# ProDoc_HyperCardReader_2024-07-05.net
KiCad netlist of a schematic drawn in EasyEDA Pro
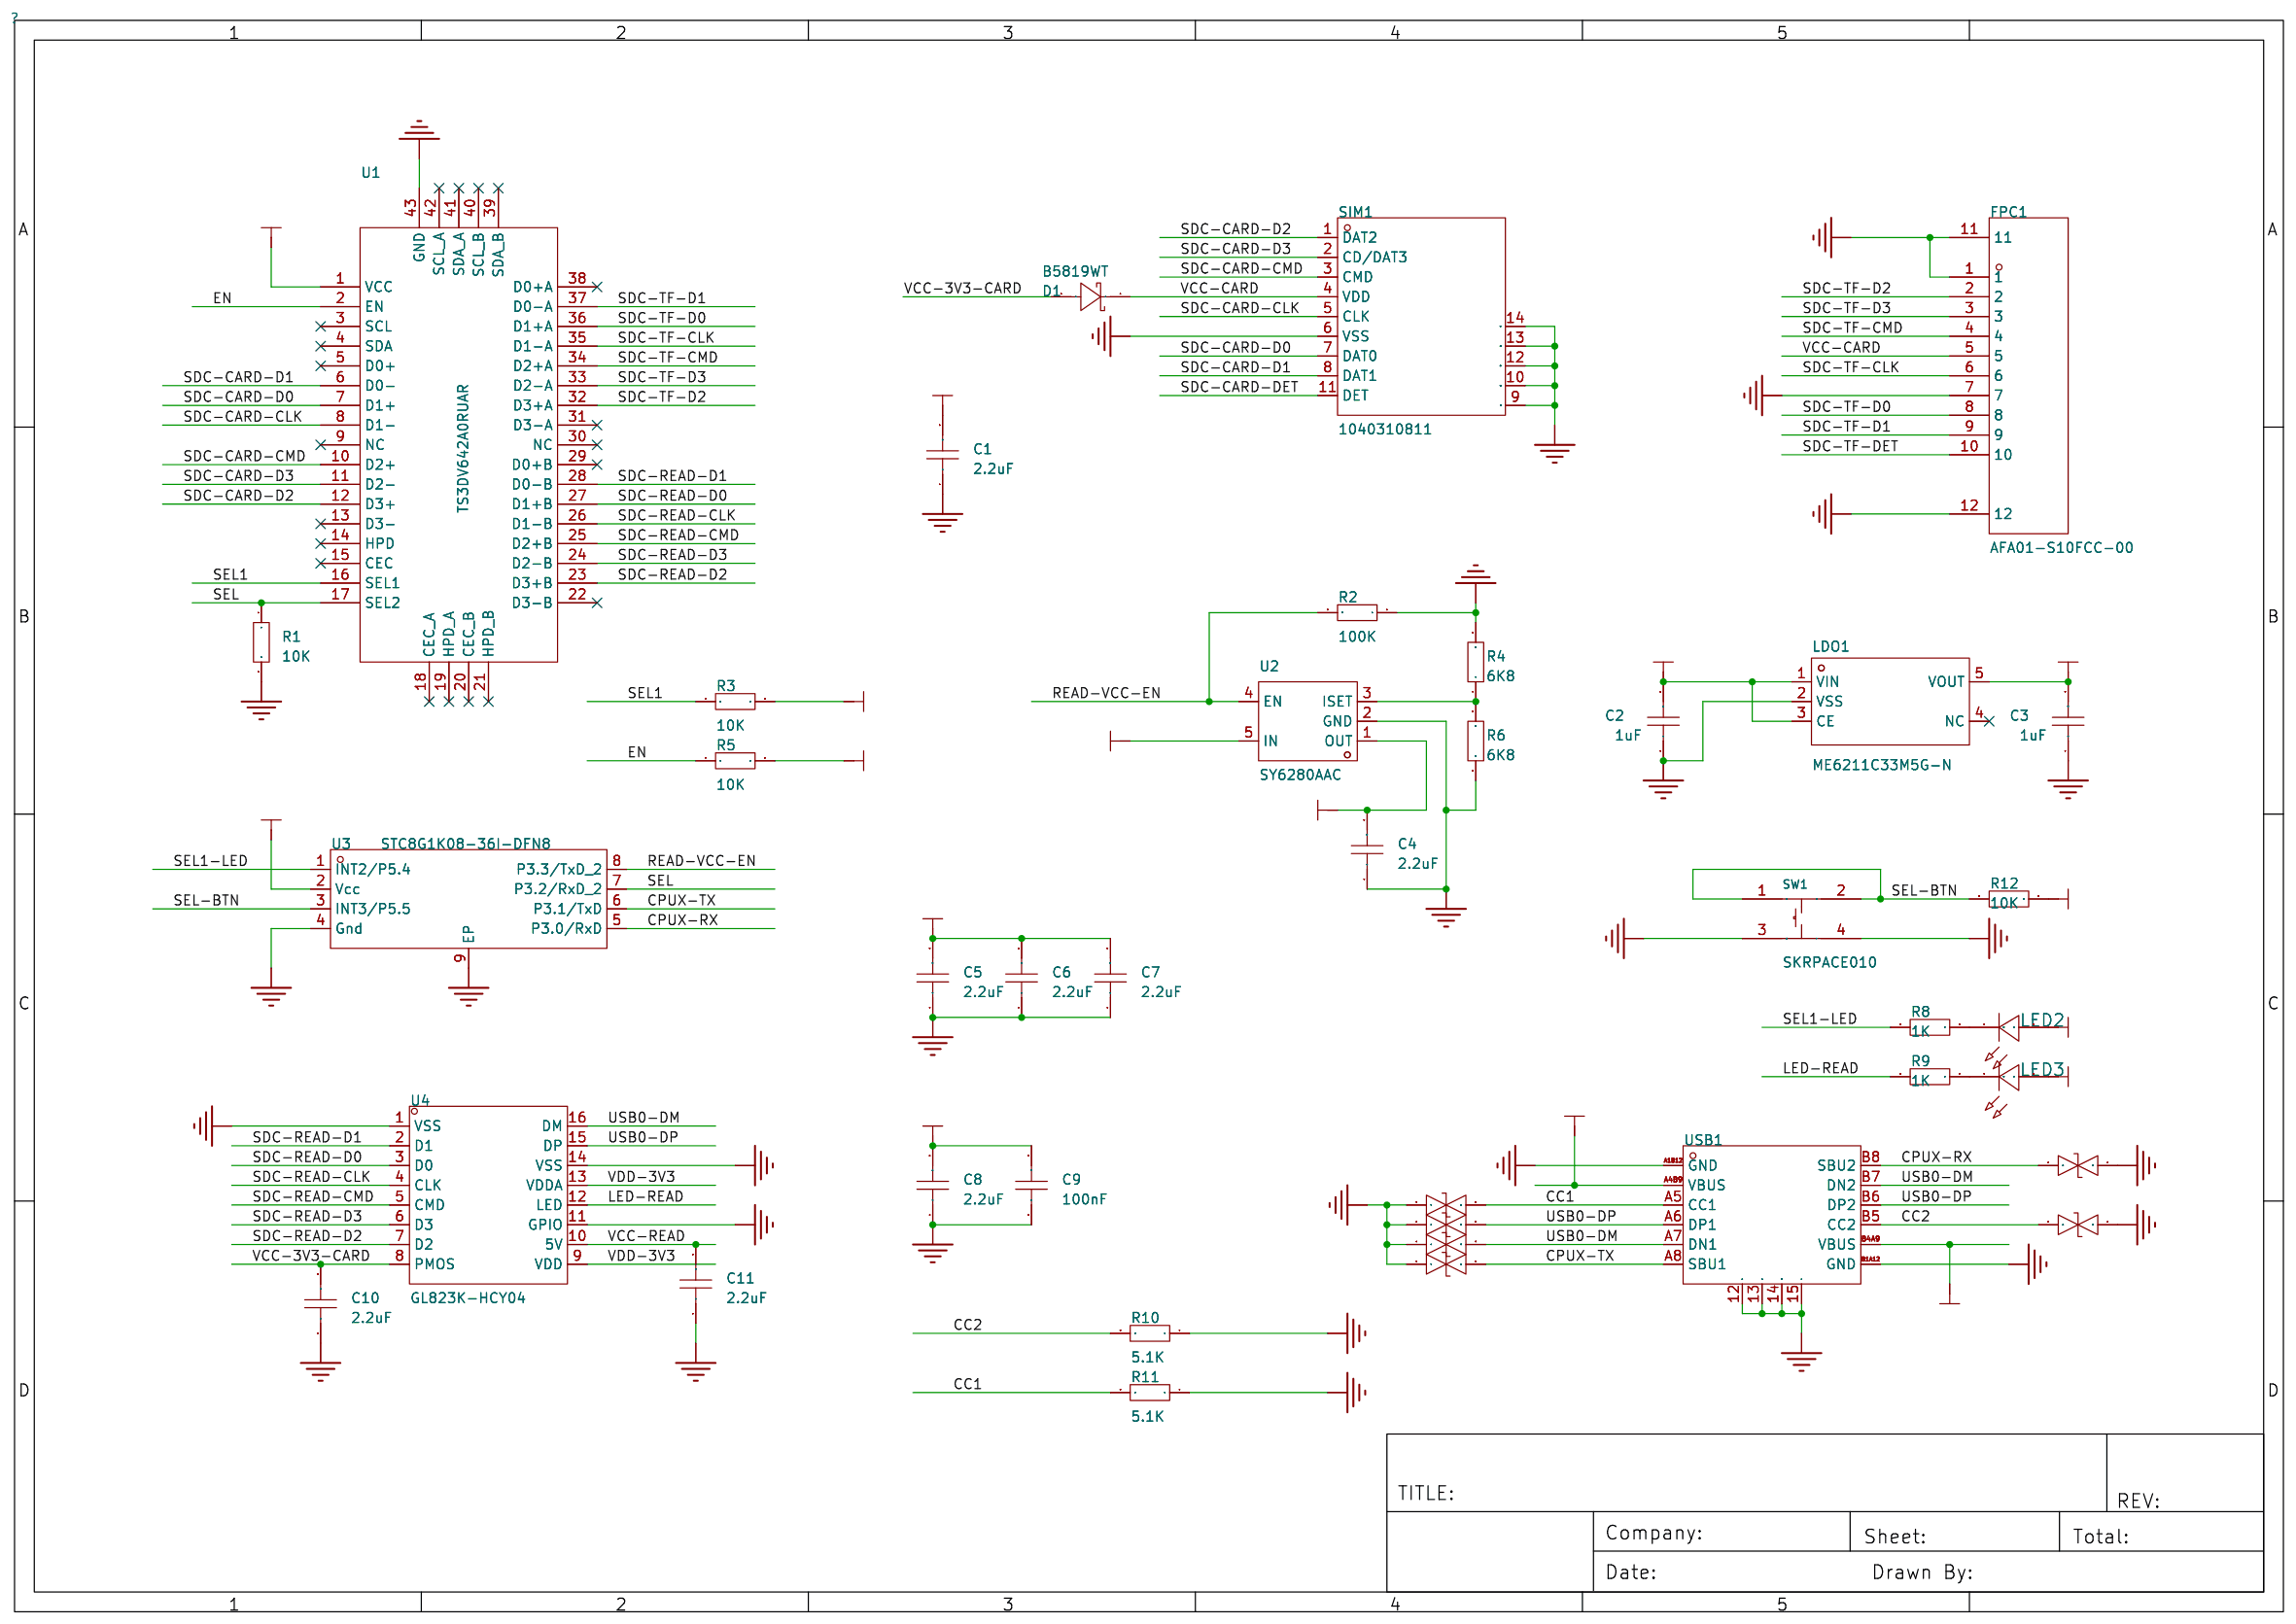
[diagram p0: schematic sheet]

(export (version "E")
  (design (tool "Eeschema 10.0.6"))
  (components
    (comp (ref "C1")
      (value "2.2uF")
      (footprint "easyedapro:C0402")
      (libsource (lib "easyedapro") (part "CapAcitance"))
    )
    (comp (ref "C2")
      (value "1uF")
      (footprint "easyedapro:C0402")
      (libsource (lib "easyedapro") (part "CapAcitance"))
    )
    (comp (ref "C3")
      (value "1uF")
      (footprint "easyedapro:C0402")
      (libsource (lib "easyedapro") (part "CapAcitance"))
    )
    (comp (ref "C4")
      (value "2.2uF")
      (footprint "easyedapro:C0402")
      (libsource (lib "easyedapro") (part "CapAcitance"))
    )
    (comp (ref "C5")
      (value "2.2uF")
      (footprint "easyedapro:C0402")
      (libsource (lib "easyedapro") (part "CapAcitance"))
    )
    (comp (ref "C6")
      (value "2.2uF")
      (footprint "easyedapro:C0402")
      (libsource (lib "easyedapro") (part "CapAcitance"))
    )
    (comp (ref "C7")
      (value "2.2uF")
      (footprint "easyedapro:C0402")
      (libsource (lib "easyedapro") (part "CapAcitance"))
    )
    (comp (ref "C8")
      (value "2.2uF")
      (footprint "easyedapro:C0402")
      (libsource (lib "easyedapro") (part "CapAcitance"))
    )
    (comp (ref "C9")
      (value "100nF")
      (footprint "easyedapro:C0402")
      (libsource (lib "easyedapro") (part "CapAcitance"))
    )
    (comp (ref "C10")
      (value "2.2uF")
      (footprint "easyedapro:C0402")
      (libsource (lib "easyedapro") (part "CapAcitance"))
    )
    (comp (ref "C11")
      (value "2.2uF")
      (footprint "easyedapro:C0402")
      (libsource (lib "easyedapro") (part "CapAcitance"))
    )
    (comp (ref "D1")
      (value "B5819WT")
      (footprint "easyedapro:SOD-523_L1.2-W0.8-LS1.6-RD")
      (description "二极管配置:-;正向压降(Vf):600mV@200mA;直流反向耐压(Vr):40V;平均整流电流(Io):1A;")
      (fields (field (name "Manufacturer") "BORN(伯恩半导体)"))
      (libsource (lib "easyedapro") (part "B5819WT_C2997265"))
    )
    (comp (ref "D2")
      (value "0402ESDA-05N")
      (footprint "easyedapro:D0402-BI")
      (description "极性:Bidirectional;反向关断电压（典型值）:5V;击穿电压（最小值）:-;箝位电压:50V;峰值脉冲电流（10/1000us）:-;")
      (fields (field (name "Manufacturer") "BORN伯恩半导体"))
      (libsource (lib "easyedapro") (part "0402ESDA-05N"))
    )
    (comp (ref "D3")
      (value "0402ESDA-05N")
      (footprint "easyedapro:D0402-BI")
      (description "极性:Bidirectional;反向关断电压（典型值）:5V;击穿电压（最小值）:-;箝位电压:50V;峰值脉冲电流（10/1000us）:-;")
      (fields (field (name "Manufacturer") "BORN伯恩半导体"))
      (libsource (lib "easyedapro") (part "0402ESDA-05N"))
    )
    (comp (ref "D4")
      (value "0402ESDA-05N")
      (footprint "easyedapro:D0402-BI")
      (description "极性:Bidirectional;反向关断电压（典型值）:5V;击穿电压（最小值）:-;箝位电压:50V;峰值脉冲电流（10/1000us）:-;")
      (fields (field (name "Manufacturer") "BORN伯恩半导体"))
      (libsource (lib "easyedapro") (part "0402ESDA-05N"))
    )
    (comp (ref "D5")
      (value "0402ESDA-05N")
      (footprint "easyedapro:D0402-BI")
      (description "极性:Bidirectional;反向关断电压（典型值）:5V;击穿电压（最小值）:-;箝位电压:50V;峰值脉冲电流（10/1000us）:-;")
      (fields (field (name "Manufacturer") "BORN伯恩半导体"))
      (libsource (lib "easyedapro") (part "0402ESDA-05N"))
    )
    (comp (ref "D6")
      (value "0402ESDA-05N")
      (footprint "easyedapro:D0402-BI")
      (description "极性:Bidirectional;反向关断电压（典型值）:5V;击穿电压（最小值）:-;箝位电压:50V;峰值脉冲电流（10/1000us）:-;")
      (fields (field (name "Manufacturer") "BORN伯恩半导体"))
      (libsource (lib "easyedapro") (part "0402ESDA-05N"))
    )
    (comp (ref "D7")
      (value "0402ESDA-05N")
      (footprint "easyedapro:D0402-BI")
      (description "极性:Bidirectional;反向关断电压（典型值）:5V;击穿电压（最小值）:-;箝位电压:50V;峰值脉冲电流（10/1000us）:-;")
      (fields (field (name "Manufacturer") "BORN伯恩半导体"))
      (libsource (lib "easyedapro") (part "0402ESDA-05N"))
    )
    (comp (ref "FPC1")
      (value "AFA01-S10FCC-00")
      (footprint "easyedapro:FPC-SMD_AFA01-S10FCC-00")
      (description "锁定特性:翻盖式;触点类型:下接;触点数量:10P;间距:1mm;安装类型:卧贴;")
      (fields (field (name "Manufacturer") "JS(钜硕电子)"))
      (libsource (lib "easyedapro") (part "AFA01-S10FCC-00"))
    )
    (comp (ref "LDO1")
      (value "ME6211C33M5G-N")
      (footprint "easyedapro:SOT-23-5_L3.0-W1.7-P0.95-LS2.8-BL")
      (description "输出类型:固定;最大输入电压:6V;输出电压:3.3V;最大输出电流:500mA;电源纹波抑制比(PSRR):70dB;输出极性:正极;")
      (fields (field (name "Manufacturer") "MICRONE(南京微盟)"))
      (libsource (lib "easyedapro") (part "ME6211C33M5G-N"))
    )
    (comp (ref "LED2")
      (value "~")
      (footprint "easyedapro:LED_0603")
      (libsource (lib "easyedapro") (part "LED_R"))
    )
    (comp (ref "LED3")
      (value "~")
      (footprint "easyedapro:LED_0603")
      (libsource (lib "easyedapro") (part "LED_R"))
    )
    (comp (ref "R1") (value "10K") (footprint "easyedapro:R0201") (libsource (lib "easyedapro") (part "电阻")))
    (comp (ref "R2") (value "100K") (footprint "easyedapro:R0201") (libsource (lib "easyedapro") (part "电阻")))
    (comp (ref "R3") (value "10K") (footprint "easyedapro:R0201") (libsource (lib "easyedapro") (part "电阻")))
    (comp (ref "R4") (value "6K8") (footprint "easyedapro:R0201") (libsource (lib "easyedapro") (part "电阻")))
    (comp (ref "R5") (value "10K") (footprint "easyedapro:R0201") (libsource (lib "easyedapro") (part "电阻")))
    (comp (ref "R6") (value "6K8") (footprint "easyedapro:R0201") (libsource (lib "easyedapro") (part "电阻")))
    (comp (ref "R8") (value "1K") (footprint "easyedapro:R0201") (libsource (lib "easyedapro") (part "电阻")))
    (comp (ref "R9") (value "1K") (footprint "easyedapro:R0201") (libsource (lib "easyedapro") (part "电阻")))
    (comp (ref "R10")
      (value "5.1K")
      (footprint "easyedapro:R0201")
      (libsource (lib "easyedapro") (part "电阻"))
    )
    (comp (ref "R11")
      (value "5.1K")
      (footprint "easyedapro:R0201")
      (libsource (lib "easyedapro") (part "电阻"))
    )
    (comp (ref "R12") (value "10K") (footprint "easyedapro:R0201") (libsource (lib "easyedapro") (part "电阻")))
    (comp (ref "SIM1")
      (value "1040310811")
      (footprint "easyedapro:SIM-SMD_8P-1040310811")
      (description "卡连接方式:拔插式;卡类型:MicroSD卡(TF卡);连接器类型:卡座;本体最大高度:1.42mm;触头镀层:金;工作温度范围:-;")
      (fields (field (name "Manufacturer") "MOLEX"))
      (libsource (lib "easyedapro") (part "1040310811"))
    )
    (comp (ref "SW1")
      (value "SKRPACE010")
      (footprint "easyedapro:KEY-SMD_4P-L4.2-W3.2-P2.20-LS4.6")
      (description "电路结构:单刀单掷;按钮形状:椭圆形按钮;安装方式:立贴;开关长度:4.2mm;开关宽度:3.2mm;开关高度:2.5mm;触点电流:50mA;额定电压(DC):16V;带灯:-;机械寿命:-;")
      (fields (field (name "Manufacturer") "ALPSALPINE(阿尔卑斯阿尔派)"))
      (libsource (lib "easyedapro") (part "SKRPACE010"))
    )
    (comp (ref "U1")
      (value "TS3DV642A0RUAR")
      (footprint "easyedapro:WFQFN-42_L9.0-W3.5-P0.50-BL-EP")
      (description "开关电路:-;")
      (fields (field (name "Manufacturer") "TI(德州仪器)"))
      (libsource (lib "easyedapro") (part "TS3DV642A0RUAR"))
    )
    (comp (ref "U2")
      (value "SY6280AAC")
      (footprint "easyedapro:SOT-23-5_L3.0-W1.7-P0.95-LS2.8-BL")
      (description "低能耗配电开关")
      (fields (field (name "Manufacturer") "silergy(矽力杰)"))
      (libsource (lib "easyedapro") (part "SY6280AAC"))
    )
    (comp (ref "U3")
      (value "STC8G1K08-36I-DFN8")
      (footprint "easyedapro:DFN-8_L3.0-W3.0-P0.50-BL-EP")
      (description "CPU内核:51系列;程序存储容量:8KB;RAM总容量:1.25KB;GPIO端口数量:6;工作电压范围:1.9V~5.5V;CPU最大主频:-;程序存储器类型:FLASH;")
      (fields (field (name "Manufacturer") "STC(宏晶)"))
      (libsource (lib "easyedapro") (part "STC8G1K08-36I-DFN8"))
    )
    (comp (ref "U4")
      (value "GL823K-HCY04")
      (footprint "easyedapro:SSOP-16_L4.9-W3.9-P0.64-LS6.0-BL")
      (description "应用功能:-;接口协议:-;")
      (fields (field (name "Manufacturer") "GENESYS(创惟)"))
      (libsource (lib "easyedapro") (part "GL823K-HCY04"))
    )
    (comp (ref "USB1")
      (value "~")
      (footprint "easyedapro:USB-C-SMD_TYPEC-304-BCP16-1")
      (fields (field (name "Manufacturer Part") "TYPEC-304-BCP16") (field (name "Manufacturer") "XUNPU"))
      (libsource (lib "easyedapro") (part "TYPEC-304-BCP16"))
    )
  )
  (nets
    (net (code "1") (name "/CC1") (class "Default")
      (node (ref "D3") (pin "2") (pinfunction "2_2") (pintype "unspecified"))
      (node (ref "R11") (pin "2") (pinfunction "2_2") (pintype "input"))
      (node (ref "USB1") (pin "A5") (pinfunction "CC1_A5") (pintype "unspecified"))
    )
    (net (code "2") (name "/CC2") (class "Default")
      (node (ref "D6") (pin "2") (pinfunction "2_2") (pintype "unspecified"))
      (node (ref "R10") (pin "2") (pinfunction "2_2") (pintype "input"))
      (node (ref "USB1") (pin "B5") (pinfunction "CC2_B5") (pintype "unspecified"))
    )
    (net (code "3") (name "/CPUX-RX") (class "Default")
      (node (ref "D2") (pin "2") (pinfunction "2_2") (pintype "unspecified"))
      (node (ref "U3") (pin "5") (pinfunction "P3.0/RxD_5") (pintype "input"))
      (node (ref "USB1") (pin "B8") (pinfunction "SBU2_B8") (pintype "unspecified"))
    )
    (net (code "4") (name "/CPUX-TX") (class "Default")
      (node (ref "D7") (pin "2") (pinfunction "2_2") (pintype "unspecified"))
      (node (ref "U3") (pin "6") (pinfunction "P3.1/TxD_6") (pintype "input"))
      (node (ref "USB1") (pin "A8") (pinfunction "SBU1_A8") (pintype "unspecified"))
    )
    (net (code "5") (name "/EN") (class "Default")
      (node (ref "R5") (pin "1") (pinfunction "1_1") (pintype "input"))
      (node (ref "U1") (pin "2") (pinfunction "EN_2") (pintype "input"))
    )
    (net (code "6") (name "/LED-READ") (class "Default")
      (node (ref "R9") (pin "2") (pinfunction "2_2") (pintype "input"))
      (node (ref "U4") (pin "12") (pinfunction "LED_12") (pintype "unspecified"))
    )
    (net (code "7") (name "/READ-VCC-EN") (class "Default")
      (node (ref "R2") (pin "2") (pinfunction "2_2") (pintype "input"))
      (node (ref "U2") (pin "4") (pinfunction "EN_4") (pintype "unspecified"))
      (node (ref "U3") (pin "8") (pinfunction "P3.3/TxD_2_8") (pintype "input"))
    )
    (net (code "8") (name "/SDC-CARD-CLK") (class "Default")
      (node (ref "SIM1") (pin "5") (pinfunction "CLK_5") (pintype "input"))
      (node (ref "U1") (pin "8") (pinfunction "D1-_8") (pintype "input"))
    )
    (net (code "9") (name "/SDC-CARD-CMD") (class "Default")
      (node (ref "SIM1") (pin "3") (pinfunction "CMD_3") (pintype "input"))
      (node (ref "U1") (pin "10") (pinfunction "D2+_10") (pintype "input"))
    )
    (net (code "10") (name "/SDC-CARD-D0") (class "Default")
      (node (ref "SIM1") (pin "7") (pinfunction "DAT0_7") (pintype "input"))
      (node (ref "U1") (pin "7") (pinfunction "D1+_7") (pintype "input"))
    )
    (net (code "11") (name "/SDC-CARD-D1") (class "Default")
      (node (ref "SIM1") (pin "8") (pinfunction "DAT1_8") (pintype "input"))
      (node (ref "U1") (pin "6") (pinfunction "D0-_6") (pintype "input"))
    )
    (net (code "12") (name "/SDC-CARD-D2") (class "Default")
      (node (ref "SIM1") (pin "1") (pinfunction "DAT2_1") (pintype "input"))
      (node (ref "U1") (pin "12") (pinfunction "D3+_12") (pintype "input"))
    )
    (net (code "13") (name "/SDC-CARD-D3") (class "Default")
      (node (ref "SIM1") (pin "2") (pinfunction "CD/DAT3_2") (pintype "input"))
      (node (ref "U1") (pin "11") (pinfunction "D2-_11") (pintype "input"))
    )
    (net (code "14") (name "/SDC-CARD-DET") (class "Default")
      (node (ref "SIM1") (pin "11") (pinfunction "DET_11") (pintype "input"))
    )
    (net (code "15") (name "/SDC-READ-CLK") (class "Default")
      (node (ref "U1") (pin "26") (pinfunction "D1-B_26") (pintype "input"))
      (node (ref "U4") (pin "4") (pinfunction "CLK_4") (pintype "unspecified"))
    )
    (net (code "16") (name "/SDC-READ-CMD") (class "Default")
      (node (ref "U1") (pin "25") (pinfunction "D2+B_25") (pintype "input"))
      (node (ref "U4") (pin "5") (pinfunction "CMD_5") (pintype "unspecified"))
    )
    (net (code "17") (name "/SDC-READ-D0") (class "Default")
      (node (ref "U1") (pin "27") (pinfunction "D1+B_27") (pintype "input"))
      (node (ref "U4") (pin "3") (pinfunction "D0_3") (pintype "unspecified"))
    )
    (net (code "18") (name "/SDC-READ-D1") (class "Default")
      (node (ref "U1") (pin "28") (pinfunction "D0-B_28") (pintype "input"))
      (node (ref "U4") (pin "2") (pinfunction "D1_2") (pintype "unspecified"))
    )
    (net (code "19") (name "/SDC-READ-D2") (class "Default")
      (node (ref "U1") (pin "23") (pinfunction "D3+B_23") (pintype "input"))
      (node (ref "U4") (pin "7") (pinfunction "D2_7") (pintype "unspecified"))
    )
    (net (code "20") (name "/SDC-READ-D3") (class "Default")
      (node (ref "U1") (pin "24") (pinfunction "D2-B_24") (pintype "input"))
      (node (ref "U4") (pin "6") (pinfunction "D3_6") (pintype "unspecified"))
    )
    (net (code "21") (name "/SDC-TF-CLK") (class "Default")
      (node (ref "FPC1") (pin "6") (pinfunction "6_6") (pintype "unspecified"))
      (node (ref "U1") (pin "35") (pinfunction "D1-A_35") (pintype "input"))
    )
    (net (code "22") (name "/SDC-TF-CMD") (class "Default")
      (node (ref "FPC1") (pin "4") (pinfunction "4_4") (pintype "unspecified"))
      (node (ref "U1") (pin "34") (pinfunction "D2+A_34") (pintype "input"))
    )
    (net (code "23") (name "/SDC-TF-D0") (class "Default")
      (node (ref "FPC1") (pin "8") (pinfunction "8_8") (pintype "unspecified"))
      (node (ref "U1") (pin "36") (pinfunction "D1+A_36") (pintype "input"))
    )
    (net (code "24") (name "/SDC-TF-D1") (class "Default")
      (node (ref "FPC1") (pin "9") (pinfunction "9_9") (pintype "unspecified"))
      (node (ref "U1") (pin "37") (pinfunction "D0-A_37") (pintype "input"))
    )
    (net (code "25") (name "/SDC-TF-D2") (class "Default")
      (node (ref "FPC1") (pin "2") (pinfunction "2_2") (pintype "unspecified"))
      (node (ref "U1") (pin "32") (pinfunction "D3+A_32") (pintype "input"))
    )
    (net (code "26") (name "/SDC-TF-D3") (class "Default")
      (node (ref "FPC1") (pin "3") (pinfunction "3_3") (pintype "unspecified"))
      (node (ref "U1") (pin "33") (pinfunction "D2-A_33") (pintype "input"))
    )
    (net (code "27") (name "/SDC-TF-DET") (class "Default")
      (node (ref "FPC1") (pin "10") (pinfunction "10_10") (pintype "unspecified"))
    )
    (net (code "28") (name "/SEL") (class "Default")
      (node (ref "R1") (pin "1") (pinfunction "1_1") (pintype "input"))
      (node (ref "U1") (pin "17") (pinfunction "SEL2_17") (pintype "input"))
      (node (ref "U3") (pin "7") (pinfunction "P3.2/RxD_2_7") (pintype "input"))
    )
    (net (code "29") (name "/SEL-BTN") (class "Default")
      (node (ref "R12") (pin "2") (pinfunction "2_2") (pintype "input"))
      (node (ref "SW1") (pin "1") (pinfunction "1_1") (pintype "input"))
      (node (ref "SW1") (pin "2") (pinfunction "2_2") (pintype "input"))
      (node (ref "U3") (pin "3") (pinfunction "INT3/P5.5_3") (pintype "input"))
    )
    (net (code "30") (name "/SEL1") (class "Default")
      (node (ref "R3") (pin "1") (pinfunction "1_1") (pintype "input"))
      (node (ref "U1") (pin "16") (pinfunction "SEL1_16") (pintype "input"))
    )
    (net (code "31") (name "/SEL1-LED") (class "Default")
      (node (ref "R8") (pin "2") (pinfunction "2_2") (pintype "input"))
      (node (ref "U3") (pin "1") (pinfunction "INT2/P5.4_1") (pintype "input"))
    )
    (net (code "32") (name "/USB0-DM") (class "Default")
      (node (ref "D5") (pin "2") (pinfunction "2_2") (pintype "unspecified"))
      (node (ref "U4") (pin "16") (pinfunction "DM_16") (pintype "unspecified"))
      (node (ref "USB1") (pin "A7") (pinfunction "DN1_A7") (pintype "unspecified"))
      (node (ref "USB1") (pin "B7") (pinfunction "DN2_B7") (pintype "unspecified"))
    )
    (net (code "33") (name "/USB0-DP") (class "Default")
      (node (ref "D4") (pin "2") (pinfunction "2_2") (pintype "unspecified"))
      (node (ref "U4") (pin "15") (pinfunction "DP_15") (pintype "unspecified"))
      (node (ref "USB1") (pin "A6") (pinfunction "DP1_A6") (pintype "unspecified"))
      (node (ref "USB1") (pin "B6") (pinfunction "DP2_B6") (pintype "unspecified"))
    )
    (net (code "34") (name "/VCC-3V3-CARD") (class "Default")
      (node (ref "C10") (pin "2") (pinfunction "2_2") (pintype "input"))
      (node (ref "D1") (pin "2") (pinfunction "A_2") (pintype "unspecified"))
      (node (ref "U4") (pin "8") (pinfunction "PMOS_8") (pintype "unspecified"))
    )
    (net (code "35") (name "GND") (class "Default")
      (node (ref "C1") (pin "1") (pinfunction "1_1") (pintype "input"))
      (node (ref "C10") (pin "1") (pinfunction "1_1") (pintype "input"))
      (node (ref "C11") (pin "1") (pinfunction "1_1") (pintype "input"))
      (node (ref "C2") (pin "1") (pinfunction "1_1") (pintype "input"))
      (node (ref "C3") (pin "1") (pinfunction "1_1") (pintype "input"))
      (node (ref "C4") (pin "1") (pinfunction "1_1") (pintype "input"))
      (node (ref "C5") (pin "1") (pinfunction "1_1") (pintype "input"))
      (node (ref "C6") (pin "1") (pinfunction "1_1") (pintype "input"))
      (node (ref "C7") (pin "1") (pinfunction "1_1") (pintype "input"))
      (node (ref "C8") (pin "1") (pinfunction "1_1") (pintype "input"))
      (node (ref "C9") (pin "1") (pinfunction "1_1") (pintype "input"))
      (node (ref "D2") (pin "1") (pinfunction "1_1") (pintype "unspecified"))
      (node (ref "D3") (pin "1") (pinfunction "1_1") (pintype "unspecified"))
      (node (ref "D4") (pin "1") (pinfunction "1_1") (pintype "unspecified"))
      (node (ref "D5") (pin "1") (pinfunction "1_1") (pintype "unspecified"))
      (node (ref "D6") (pin "1") (pinfunction "1_1") (pintype "unspecified"))
      (node (ref "D7") (pin "1") (pinfunction "1_1") (pintype "unspecified"))
      (node (ref "FPC1") (pin "1") (pinfunction "1_1") (pintype "unspecified"))
      (node (ref "FPC1") (pin "11") (pinfunction "11_11") (pintype "unspecified"))
      (node (ref "FPC1") (pin "12") (pinfunction "12_12") (pintype "unspecified"))
      (node (ref "FPC1") (pin "7") (pinfunction "7_7") (pintype "unspecified"))
      (node (ref "LDO1") (pin "2") (pinfunction "VSS_2") (pintype "input"))
      (node (ref "R1") (pin "2") (pinfunction "2_2") (pintype "input"))
      (node (ref "R10") (pin "1") (pinfunction "1_1") (pintype "input"))
      (node (ref "R11") (pin "1") (pinfunction "1_1") (pintype "input"))
      (node (ref "R2") (pin "1") (pinfunction "1_1") (pintype "input"))
      (node (ref "R4") (pin "2") (pinfunction "2_2") (pintype "input"))
      (node (ref "R6") (pin "1") (pinfunction "1_1") (pintype "input"))
      (node (ref "SIM1") (pin "10") (pinfunction "10_10") (pintype "input"))
      (node (ref "SIM1") (pin "12") (pinfunction "12_12") (pintype "input"))
      (node (ref "SIM1") (pin "13") (pinfunction "13_13") (pintype "input"))
      (node (ref "SIM1") (pin "14") (pinfunction "14_14") (pintype "input"))
      (node (ref "SIM1") (pin "6") (pinfunction "VSS_6") (pintype "input"))
      (node (ref "SIM1") (pin "9") (pinfunction "9_9") (pintype "input"))
      (node (ref "SW1") (pin "3") (pinfunction "3_3") (pintype "input"))
      (node (ref "SW1") (pin "4") (pinfunction "4_4") (pintype "input"))
      (node (ref "U1") (pin "43") (pinfunction "GND_43") (pintype "input"))
      (node (ref "U2") (pin "2") (pinfunction "GND_2") (pintype "unspecified"))
      (node (ref "U3") (pin "4") (pinfunction "Gnd_4") (pintype "input"))
      (node (ref "U3") (pin "9") (pinfunction "EP_9") (pintype "input"))
      (node (ref "U4") (pin "1") (pinfunction "VSS_1") (pintype "unspecified"))
      (node (ref "U4") (pin "11") (pinfunction "GPIO_11") (pintype "unspecified"))
      (node (ref "U4") (pin "14") (pinfunction "VSS_14") (pintype "unspecified"))
      (node (ref "USB1") (pin "12") (pinfunction "1_12") (pintype "unspecified"))
      (node (ref "USB1") (pin "13") (pinfunction "2_13") (pintype "unspecified"))
      (node (ref "USB1") (pin "14") (pinfunction "3_14") (pintype "unspecified"))
      (node (ref "USB1") (pin "15") (pinfunction "4_15") (pintype "unspecified"))
      (node (ref "USB1") (pin "A1B12") (pinfunction "GND_A1B12") (pintype "unspecified"))
      (node (ref "USB1") (pin "B1A12") (pinfunction "GND_B1A12") (pintype "unspecified"))
    )
    (net (code "36") (name "Net-(LED2-C)") (class "Default")
      (node (ref "LED2") (pin "1") (pinfunction "C_1") (pintype "input"))
      (node (ref "R8") (pin "1") (pinfunction "1_1") (pintype "input"))
    )
    (net (code "37") (name "Net-(LED3-C)") (class "Default")
      (node (ref "LED3") (pin "1") (pinfunction "C_1") (pintype "input"))
      (node (ref "R9") (pin "1") (pinfunction "1_1") (pintype "input"))
    )
    (net (code "38") (name "Net-(U2-ISET)") (class "Default")
      (node (ref "R4") (pin "1") (pinfunction "1_1") (pintype "input"))
      (node (ref "R6") (pin "2") (pinfunction "2_2") (pintype "input"))
      (node (ref "U2") (pin "3") (pinfunction "ISET_3") (pintype "unspecified"))
    )
    (net (code "39") (name "VBUS-USB") (class "Default")
      (node (ref "C2") (pin "2") (pinfunction "2_2") (pintype "input"))
      (node (ref "C5") (pin "2") (pinfunction "2_2") (pintype "input"))
      (node (ref "C6") (pin "2") (pinfunction "2_2") (pintype "input"))
      (node (ref "C7") (pin "2") (pinfunction "2_2") (pintype "input"))
      (node (ref "LDO1") (pin "1") (pinfunction "VIN_1") (pintype "input"))
      (node (ref "LDO1") (pin "3") (pinfunction "CE_3") (pintype "input"))
      (node (ref "U2") (pin "5") (pinfunction "IN_5") (pintype "unspecified"))
      (node (ref "U3") (pin "2") (pinfunction "Vcc_2") (pintype "input"))
      (node (ref "USB1") (pin "A4B9") (pinfunction "VBUS_A4B9") (pintype "unspecified"))
      (node (ref "USB1") (pin "B4A9") (pinfunction "VBUS_B4A9") (pintype "unspecified"))
    )
    (net (code "40") (name "VCC-3V3-LDO") (class "Default")
      (node (ref "C3") (pin "2") (pinfunction "2_2") (pintype "input"))
      (node (ref "LDO1") (pin "5") (pinfunction "VOUT_5") (pintype "input"))
      (node (ref "LED2") (pin "2") (pinfunction "A_2") (pintype "input"))
      (node (ref "R12") (pin "1") (pinfunction "1_1") (pintype "input"))
      (node (ref "R3") (pin "2") (pinfunction "2_2") (pintype "input"))
      (node (ref "R5") (pin "2") (pinfunction "2_2") (pintype "input"))
      (node (ref "U1") (pin "1") (pinfunction "VCC_1") (pintype "input"))
    )
    (net (code "41") (name "VCC-CARD") (class "Default")
      (node (ref "C1") (pin "2") (pinfunction "2_2") (pintype "input"))
      (node (ref "D1") (pin "1") (pinfunction "K_1") (pintype "unspecified"))
      (node (ref "FPC1") (pin "5") (pinfunction "5_5") (pintype "unspecified"))
      (node (ref "SIM1") (pin "4") (pinfunction "VDD_4") (pintype "input"))
    )
    (net (code "42") (name "VCC-READ") (class "Default")
      (node (ref "C11") (pin "2") (pinfunction "2_2") (pintype "input"))
      (node (ref "C4") (pin "2") (pinfunction "2_2") (pintype "input"))
      (node (ref "U2") (pin "1") (pinfunction "OUT_1") (pintype "unspecified"))
      (node (ref "U4") (pin "10") (pinfunction "5V_10") (pintype "unspecified"))
    )
    (net (code "43") (name "VDD-3V3") (class "Default")
      (node (ref "C8") (pin "2") (pinfunction "2_2") (pintype "input"))
      (node (ref "C9") (pin "2") (pinfunction "2_2") (pintype "input"))
      (node (ref "LED3") (pin "2") (pinfunction "A_2") (pintype "input"))
      (node (ref "U4") (pin "13") (pinfunction "VDDA_13") (pintype "unspecified"))
      (node (ref "U4") (pin "9") (pinfunction "VDD_9") (pintype "unspecified"))
    )
    (net (code "44") (name "unconnected-(LDO1-NC-Pad4)") (class "Default")
      (node (ref "LDO1") (pin "4") (pinfunction "NC_4") (pintype "input+no_connect"))
    )
    (net (code "45") (name "unconnected-(U1-CEC-Pad15)") (class "Default")
      (node (ref "U1") (pin "15") (pinfunction "CEC_15") (pintype "input+no_connect"))
    )
    (net (code "46") (name "unconnected-(U1-CEC_A-Pad18)") (class "Default")
      (node (ref "U1") (pin "18") (pinfunction "CEC_A_18") (pintype "input+no_connect"))
    )
    (net (code "47") (name "unconnected-(U1-CEC_B-Pad20)") (class "Default")
      (node (ref "U1") (pin "20") (pinfunction "CEC_B_20") (pintype "input+no_connect"))
    )
    (net (code "48") (name "unconnected-(U1-D0+-Pad5)") (class "Default")
      (node (ref "U1") (pin "5") (pinfunction "D0+_5") (pintype "input+no_connect"))
    )
    (net (code "49") (name "unconnected-(U1-D0+A-Pad38)") (class "Default")
      (node (ref "U1") (pin "38") (pinfunction "D0+A_38") (pintype "input+no_connect"))
    )
    (net (code "50") (name "unconnected-(U1-D0+B-Pad29)") (class "Default")
      (node (ref "U1") (pin "29") (pinfunction "D0+B_29") (pintype "input+no_connect"))
    )
    (net (code "51") (name "unconnected-(U1-D3--Pad13)") (class "Default")
      (node (ref "U1") (pin "13") (pinfunction "D3-_13") (pintype "input+no_connect"))
    )
    (net (code "52") (name "unconnected-(U1-D3-A-Pad31)") (class "Default")
      (node (ref "U1") (pin "31") (pinfunction "D3-A_31") (pintype "input+no_connect"))
    )
    (net (code "53") (name "unconnected-(U1-D3-B-Pad22)") (class "Default")
      (node (ref "U1") (pin "22") (pinfunction "D3-B_22") (pintype "input+no_connect"))
    )
    (net (code "54") (name "unconnected-(U1-HPD-Pad14)") (class "Default")
      (node (ref "U1") (pin "14") (pinfunction "HPD_14") (pintype "input+no_connect"))
    )
    (net (code "55") (name "unconnected-(U1-HPD_A-Pad19)") (class "Default")
      (node (ref "U1") (pin "19") (pinfunction "HPD_A_19") (pintype "input+no_connect"))
    )
    (net (code "56") (name "unconnected-(U1-HPD_B-Pad21)") (class "Default")
      (node (ref "U1") (pin "21") (pinfunction "HPD_B_21") (pintype "input+no_connect"))
    )
    (net (code "57") (name "unconnected-(U1-NC-Pad9)") (class "Default")
      (node (ref "U1") (pin "9") (pinfunction "NC_9") (pintype "input+no_connect"))
    )
    (net (code "58") (name "unconnected-(U1-NC-Pad30)") (class "Default")
      (node (ref "U1") (pin "30") (pinfunction "NC_30") (pintype "input+no_connect"))
    )
    (net (code "59") (name "unconnected-(U1-SCL-Pad3)") (class "Default")
      (node (ref "U1") (pin "3") (pinfunction "SCL_3") (pintype "input+no_connect"))
    )
    (net (code "60") (name "unconnected-(U1-SCL_A-Pad42)") (class "Default")
      (node (ref "U1") (pin "42") (pinfunction "SCL_A_42") (pintype "input+no_connect"))
    )
    (net (code "61") (name "unconnected-(U1-SCL_B-Pad40)") (class "Default")
      (node (ref "U1") (pin "40") (pinfunction "SCL_B_40") (pintype "input+no_connect"))
    )
    (net (code "62") (name "unconnected-(U1-SDA-Pad4)") (class "Default")
      (node (ref "U1") (pin "4") (pinfunction "SDA_4") (pintype "input+no_connect"))
    )
    (net (code "63") (name "unconnected-(U1-SDA_A-Pad41)") (class "Default")
      (node (ref "U1") (pin "41") (pinfunction "SDA_A_41") (pintype "input+no_connect"))
    )
    (net (code "64") (name "unconnected-(U1-SDA_B-Pad39)") (class "Default")
      (node (ref "U1") (pin "39") (pinfunction "SDA_B_39") (pintype "input+no_connect"))
    )
  )
)
